# ESP32_Receptor.net
KiCad netlist of a schematic drawn in EAGLE
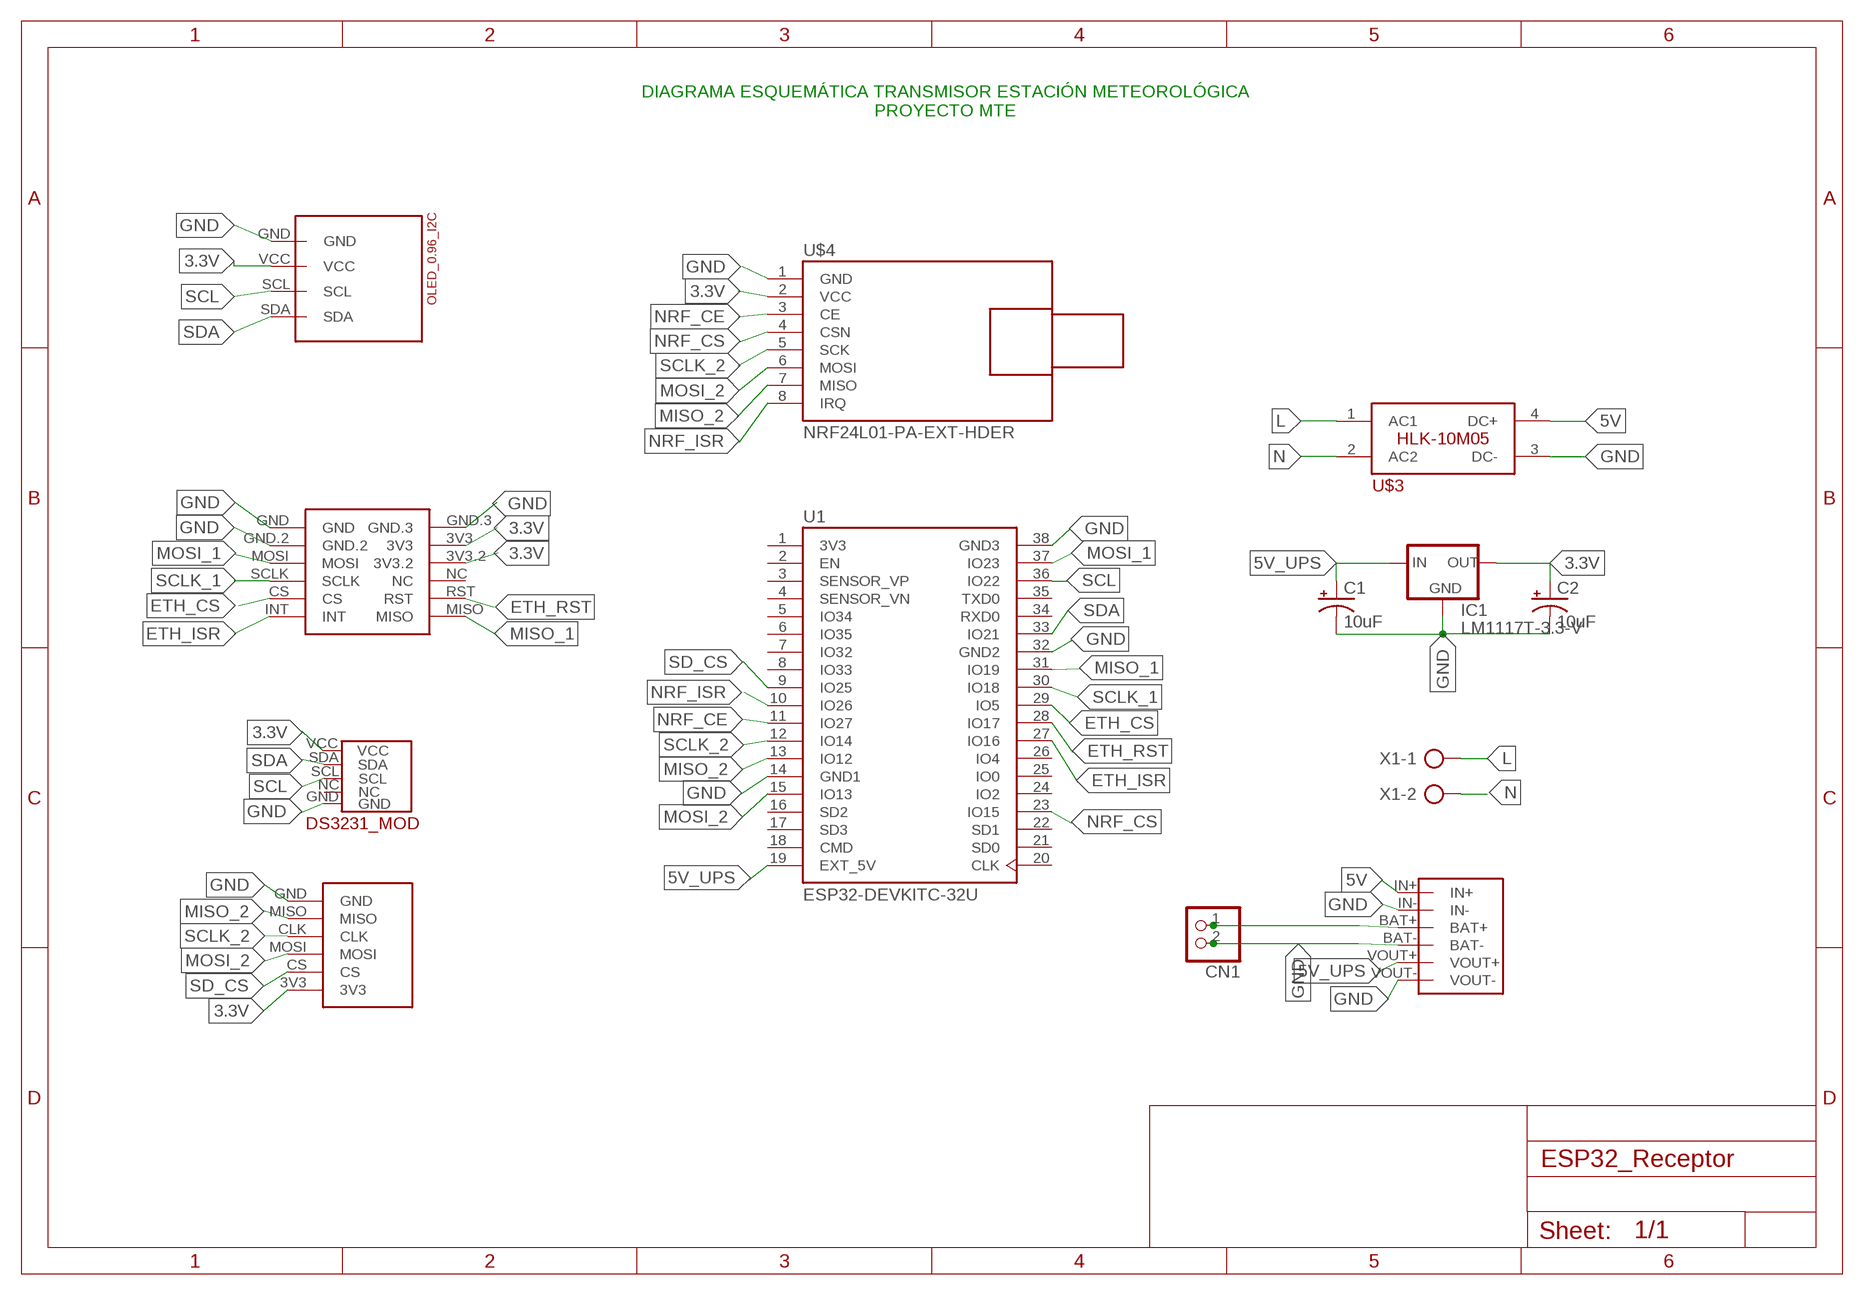
[diagram p0: schematic, sheet 1]

(export (version "E")
  (design (tool "Eeschema 10.0.6"))
  (components
    (comp (ref "C1")
      (value "10uF")
      (footprint "eagle-import:CPOL-RADIAL-2.5MM-5MM")
      (libsource (lib "eagle-import") (part "10UF-POLAR-RADIAL-2.5MM-25V-20%"))
    )
    (comp (ref "C2")
      (value "10uF")
      (footprint "eagle-import:CPOL-RADIAL-2.5MM-5MM")
      (libsource (lib "eagle-import") (part "10UF-POLAR-RADIAL-2.5MM-25V-20%"))
    )
    (comp (ref "CN1")
      (value "JST_2PIN-THM")
      (footprint "eagle-import:JST-PH-2-THM")
      (libsource (lib "eagle-import") (part "JST_2PIN-THM"))
    )
    (comp (ref "IC1")
      (value "LM1117T-3.3-V")
      (footprint "eagle-import:TO220V")
      (libsource (lib "eagle-import") (part "LM1117T--V3.3"))
    )
    (comp (ref "U$1")
      (value "MINI_W5500")
      (footprint "eagle-import:MINI_W5500")
      (libsource (lib "eagle-import") (part "MINI_W5500"))
    )
    (comp (ref "U$2")
      (value "DS3231_MOD")
      (footprint "eagle-import:DS3231_MOD")
      (libsource (lib "eagle-import") (part "DS3231_MOD"))
    )
    (comp (ref "U$3")
      (value "HLK-10M05")
      (footprint "eagle-import:HLK-10M05")
      (fields (field (name "MF") "Hi-link") (field (name "MP") "hlk-pm01"))
      (libsource (lib "eagle-import") (part "HLK-10M05"))
    )
    (comp (ref "U$4")
      (value "NRF24L01-PA-EXT-HDER")
      (footprint "eagle-import:NRF24L01-HEADER")
      (libsource (lib "eagle-import") (part "NRF24L01-PA-EXT-HDER"))
    )
    (comp (ref "U$5")
      (value "OLED_I2C_096")
      (footprint "eagle-import:OLED_096_I2C")
      (libsource (lib "eagle-import") (part "OLED_I2C_096"))
    )
    (comp (ref "U$6")
      (value "MODULO_MSD2")
      (footprint "eagle-import:MICROSD-BREAKOUT")
      (libsource (lib "eagle-import") (part "MODULO_MSD2"))
    )
    (comp (ref "U$7")
      (value "J5019_UPS")
      (footprint "eagle-import:J5019_UPS")
      (libsource (lib "eagle-import") (part "J5019_UPS"))
    )
    (comp (ref "U1")
      (value "ESP32-DEVKITC-32U")
      (footprint "eagle-import:MODULE_ESP32-DEVKITC-32U")
      (fields (field (name "MF") "Espressif Systems"))
      (libsource (lib "eagle-import") (part "ESP32-DEVKITC-32U"))
    )
    (comp (ref "X1")
      (value "AK500/2-H")
      (footprint "eagle-import:AK500_2-H")
      (libsource (lib "eagle-import") (part "AK500/2-H"))
    )
  )
  (nets
    (net (code "1") (name "/3V3") (class "Default")
      (node (ref "U1") (pin "1") (pinfunction "3V3_1") (pintype "power_in"))
    )
    (net (code "2") (name "3.3V") (class "Default")
      (node (ref "C2") (pin "1") (pinfunction "+_1") (pintype "passive"))
      (node (ref "IC1") (pin "2") (pinfunction "OUT_2") (pintype "passive"))
      (node (ref "U$1") (pin "3V3") (pinfunction "3V3_3V3") (pintype "bidirectional"))
      (node (ref "U$1") (pin "3V3.2") (pinfunction "3V3.2_3V3.2") (pintype "bidirectional"))
      (node (ref "U$2") (pin "VCC") (pinfunction "VCC_VCC") (pintype "bidirectional"))
      (node (ref "U$4") (pin "2") (pinfunction "VCC_2") (pintype "power_in"))
      (node (ref "U$5") (pin "VCC") (pinfunction "VCC_VCC") (pintype "power_in"))
      (node (ref "U$6") (pin "3V3") (pinfunction "3V3_3V3") (pintype "bidirectional"))
    )
    (net (code "3") (name "5V") (class "Default")
      (node (ref "U$3") (pin "4") (pinfunction "DC+_4") (pintype "power_in"))
      (node (ref "U$7") (pin "IN+") (pinfunction "IN+_IN+") (pintype "bidirectional"))
    )
    (net (code "4") (name "5V_UPS") (class "Default")
      (node (ref "C1") (pin "1") (pinfunction "+_1") (pintype "passive"))
      (node (ref "IC1") (pin "3") (pinfunction "IN_3") (pintype "input"))
      (node (ref "U$7") (pin "VOUT+") (pinfunction "VOUT+_VOUT+") (pintype "bidirectional"))
      (node (ref "U1") (pin "19") (pinfunction "EXT_5V_19") (pintype "power_in"))
    )
    (net (code "5") (name "ETH_CS") (class "Default")
      (node (ref "U$1") (pin "CS") (pinfunction "CS_CS") (pintype "bidirectional"))
      (node (ref "U1") (pin "29") (pinfunction "IO5_29") (pintype "bidirectional"))
    )
    (net (code "6") (name "ETH_ISR") (class "Default")
      (node (ref "U$1") (pin "INT") (pinfunction "INT_INT") (pintype "bidirectional"))
      (node (ref "U1") (pin "27") (pinfunction "IO16_27") (pintype "bidirectional"))
    )
    (net (code "7") (name "ETH_RST") (class "Default")
      (node (ref "U$1") (pin "RST") (pinfunction "RST_RST") (pintype "bidirectional"))
      (node (ref "U1") (pin "28") (pinfunction "IO17_28") (pintype "bidirectional"))
    )
    (net (code "8") (name "GND") (class "Default")
      (node (ref "C1") (pin "2") (pinfunction "-_2") (pintype "passive"))
      (node (ref "C2") (pin "2") (pinfunction "-_2") (pintype "passive"))
      (node (ref "CN1") (pin "2") (pinfunction "1_2") (pintype "passive"))
      (node (ref "IC1") (pin "1") (pinfunction "GND_1") (pintype "input"))
      (node (ref "U$1") (pin "GND") (pinfunction "GND_GND") (pintype "bidirectional"))
      (node (ref "U$1") (pin "GND.2") (pinfunction "GND.2_GND.2") (pintype "bidirectional"))
      (node (ref "U$1") (pin "GND.3") (pinfunction "GND.3_GND.3") (pintype "bidirectional"))
      (node (ref "U$2") (pin "GND") (pinfunction "GND_GND") (pintype "bidirectional"))
      (node (ref "U$3") (pin "3") (pinfunction "DC-_3") (pintype "power_in"))
      (node (ref "U$4") (pin "1") (pinfunction "GND_1") (pintype "power_in"))
      (node (ref "U$5") (pin "GND") (pinfunction "GND_GND") (pintype "power_in"))
      (node (ref "U$6") (pin "GND") (pinfunction "GND_GND") (pintype "bidirectional"))
      (node (ref "U$7") (pin "BAT-") (pinfunction "BAT-_BAT-") (pintype "bidirectional"))
      (node (ref "U$7") (pin "IN-") (pinfunction "IN-_IN-") (pintype "bidirectional"))
      (node (ref "U$7") (pin "VOUT-") (pinfunction "VOUT-_VOUT-") (pintype "bidirectional"))
      (node (ref "U1") (pin "14") (pinfunction "GND1_14") (pintype "power_in"))
      (node (ref "U1") (pin "32") (pinfunction "GND2_32") (pintype "power_in"))
      (node (ref "U1") (pin "38") (pinfunction "GND3_38") (pintype "power_in"))
    )
    (net (code "9") (name "L") (class "Default")
      (node (ref "U$3") (pin "1") (pinfunction "AC1_1") (pintype "power_in"))
      (node (ref "X1") (pin "1") (pinfunction "KL_1") (pintype "passive"))
    )
    (net (code "10") (name "MISO_1") (class "Default")
      (node (ref "U$1") (pin "MISO") (pinfunction "MISO_MISO") (pintype "bidirectional"))
      (node (ref "U1") (pin "31") (pinfunction "IO19_31") (pintype "bidirectional"))
    )
    (net (code "11") (name "MISO_2") (class "Default")
      (node (ref "U$4") (pin "7") (pinfunction "MISO_7") (pintype "bidirectional"))
      (node (ref "U$6") (pin "MISO") (pinfunction "MISO_MISO") (pintype "bidirectional"))
      (node (ref "U1") (pin "13") (pinfunction "IO12_13") (pintype "bidirectional"))
    )
    (net (code "12") (name "MOSI_1") (class "Default")
      (node (ref "U$1") (pin "MOSI") (pinfunction "MOSI_MOSI") (pintype "bidirectional"))
      (node (ref "U1") (pin "37") (pinfunction "IO23_37") (pintype "bidirectional"))
    )
    (net (code "13") (name "MOSI_2") (class "Default")
      (node (ref "U$4") (pin "6") (pinfunction "MOSI_6") (pintype "bidirectional"))
      (node (ref "U$6") (pin "MOSI") (pinfunction "MOSI_MOSI") (pintype "bidirectional"))
      (node (ref "U1") (pin "15") (pinfunction "IO13_15") (pintype "bidirectional"))
    )
    (net (code "14") (name "N") (class "Default")
      (node (ref "U$3") (pin "2") (pinfunction "AC2_2") (pintype "power_in"))
      (node (ref "X1") (pin "2") (pinfunction "KL_2") (pintype "passive"))
    )
    (net (code "15") (name "NRF_CE") (class "Default")
      (node (ref "U$4") (pin "3") (pinfunction "CE_3") (pintype "bidirectional"))
      (node (ref "U1") (pin "11") (pinfunction "IO27_11") (pintype "bidirectional"))
    )
    (net (code "16") (name "NRF_CS") (class "Default")
      (node (ref "U$4") (pin "4") (pinfunction "CSN_4") (pintype "bidirectional"))
      (node (ref "U1") (pin "23") (pinfunction "IO15_23") (pintype "bidirectional"))
    )
    (net (code "17") (name "NRF_ISR") (class "Default")
      (node (ref "U$4") (pin "8") (pinfunction "IRQ_8") (pintype "bidirectional"))
      (node (ref "U1") (pin "10") (pinfunction "IO26_10") (pintype "bidirectional"))
    )
    (net (code "18") (name "Net-(CN1-2)") (class "Default")
      (node (ref "CN1") (pin "1") (pinfunction "2_1") (pintype "passive"))
      (node (ref "U$7") (pin "BAT+") (pinfunction "BAT+_BAT+") (pintype "bidirectional"))
    )
    (net (code "19") (name "SCL") (class "Default")
      (node (ref "U$2") (pin "SCL") (pinfunction "SCL_SCL") (pintype "bidirectional"))
      (node (ref "U$5") (pin "SCL") (pinfunction "SCL_SCL") (pintype "bidirectional"))
      (node (ref "U1") (pin "36") (pinfunction "IO22_36") (pintype "bidirectional"))
    )
    (net (code "20") (name "SCLK_1") (class "Default")
      (node (ref "U$1") (pin "SCLK") (pinfunction "SCLK_SCLK") (pintype "bidirectional"))
      (node (ref "U1") (pin "30") (pinfunction "IO18_30") (pintype "bidirectional"))
    )
    (net (code "21") (name "SCLK_2") (class "Default")
      (node (ref "U$4") (pin "5") (pinfunction "SCK_5") (pintype "bidirectional"))
      (node (ref "U$6") (pin "CLK") (pinfunction "CLK_CLK") (pintype "bidirectional"))
      (node (ref "U1") (pin "12") (pinfunction "IO14_12") (pintype "bidirectional"))
    )
    (net (code "22") (name "SDA") (class "Default")
      (node (ref "U$2") (pin "SDA") (pinfunction "SDA_SDA") (pintype "bidirectional"))
      (node (ref "U$5") (pin "SDA") (pinfunction "SDA_SDA") (pintype "bidirectional"))
      (node (ref "U1") (pin "33") (pinfunction "IO21_33") (pintype "bidirectional"))
    )
    (net (code "23") (name "SD_CS") (class "Default")
      (node (ref "U$6") (pin "CS") (pinfunction "CS_CS") (pintype "bidirectional"))
      (node (ref "U1") (pin "9") (pinfunction "IO25_9") (pintype "bidirectional"))
    )
    (net (code "24") (name "unconnected-(U$1-PadNC)") (class "Default")
      (node (ref "U$1") (pin "NC") (pinfunction "NC_NC") (pintype "bidirectional"))
    )
    (net (code "25") (name "unconnected-(U$2-PadNC)") (class "Default")
      (node (ref "U$2") (pin "NC") (pinfunction "NC_NC") (pintype "bidirectional"))
    )
    (net (code "26") (name "unconnected-(U1-CLK-Pad20)") (class "Default")
      (node (ref "U1") (pin "20") (pinfunction "CLK_20") (pintype "input"))
    )
    (net (code "27") (name "unconnected-(U1-CMD-Pad18)") (class "Default")
      (node (ref "U1") (pin "18") (pinfunction "CMD_18") (pintype "bidirectional"))
    )
    (net (code "28") (name "unconnected-(U1-EN-Pad2)") (class "Default")
      (node (ref "U1") (pin "2") (pinfunction "EN_2") (pintype "input"))
    )
    (net (code "29") (name "unconnected-(U1-IO0-Pad25)") (class "Default")
      (node (ref "U1") (pin "25") (pinfunction "IO0_25") (pintype "bidirectional"))
    )
    (net (code "30") (name "unconnected-(U1-IO2-Pad24)") (class "Default")
      (node (ref "U1") (pin "24") (pinfunction "IO2_24") (pintype "bidirectional"))
    )
    (net (code "31") (name "unconnected-(U1-IO4-Pad26)") (class "Default")
      (node (ref "U1") (pin "26") (pinfunction "IO4_26") (pintype "bidirectional"))
    )
    (net (code "32") (name "unconnected-(U1-IO32-Pad7)") (class "Default")
      (node (ref "U1") (pin "7") (pinfunction "IO32_7") (pintype "bidirectional"))
    )
    (net (code "33") (name "unconnected-(U1-IO33-Pad8)") (class "Default")
      (node (ref "U1") (pin "8") (pinfunction "IO33_8") (pintype "bidirectional"))
    )
    (net (code "34") (name "unconnected-(U1-IO34-Pad5)") (class "Default")
      (node (ref "U1") (pin "5") (pinfunction "IO34_5") (pintype "bidirectional"))
    )
    (net (code "35") (name "unconnected-(U1-IO35-Pad6)") (class "Default")
      (node (ref "U1") (pin "6") (pinfunction "IO35_6") (pintype "bidirectional"))
    )
    (net (code "36") (name "unconnected-(U1-RXD0-Pad34)") (class "Default")
      (node (ref "U1") (pin "34") (pinfunction "RXD0_34") (pintype "input"))
    )
    (net (code "37") (name "unconnected-(U1-SD0-Pad21)") (class "Default")
      (node (ref "U1") (pin "21") (pinfunction "SD0_21") (pintype "bidirectional"))
    )
    (net (code "38") (name "unconnected-(U1-SD1-Pad22)") (class "Default")
      (node (ref "U1") (pin "22") (pinfunction "SD1_22") (pintype "bidirectional"))
    )
    (net (code "39") (name "unconnected-(U1-SD2-Pad16)") (class "Default")
      (node (ref "U1") (pin "16") (pinfunction "SD2_16") (pintype "bidirectional"))
    )
    (net (code "40") (name "unconnected-(U1-SD3-Pad17)") (class "Default")
      (node (ref "U1") (pin "17") (pinfunction "SD3_17") (pintype "bidirectional"))
    )
    (net (code "41") (name "unconnected-(U1-SENSOR_VN-Pad4)") (class "Default")
      (node (ref "U1") (pin "4") (pinfunction "SENSOR_VN_4") (pintype "input"))
    )
    (net (code "42") (name "unconnected-(U1-SENSOR_VP-Pad3)") (class "Default")
      (node (ref "U1") (pin "3") (pinfunction "SENSOR_VP_3") (pintype "input"))
    )
    (net (code "43") (name "unconnected-(U1-TXD0-Pad35)") (class "Default")
      (node (ref "U1") (pin "35") (pinfunction "TXD0_35") (pintype "output"))
    )
  )
)
